# YARC_ID_Timer.net
KiCad netlist of a schematic drawn in EAGLE
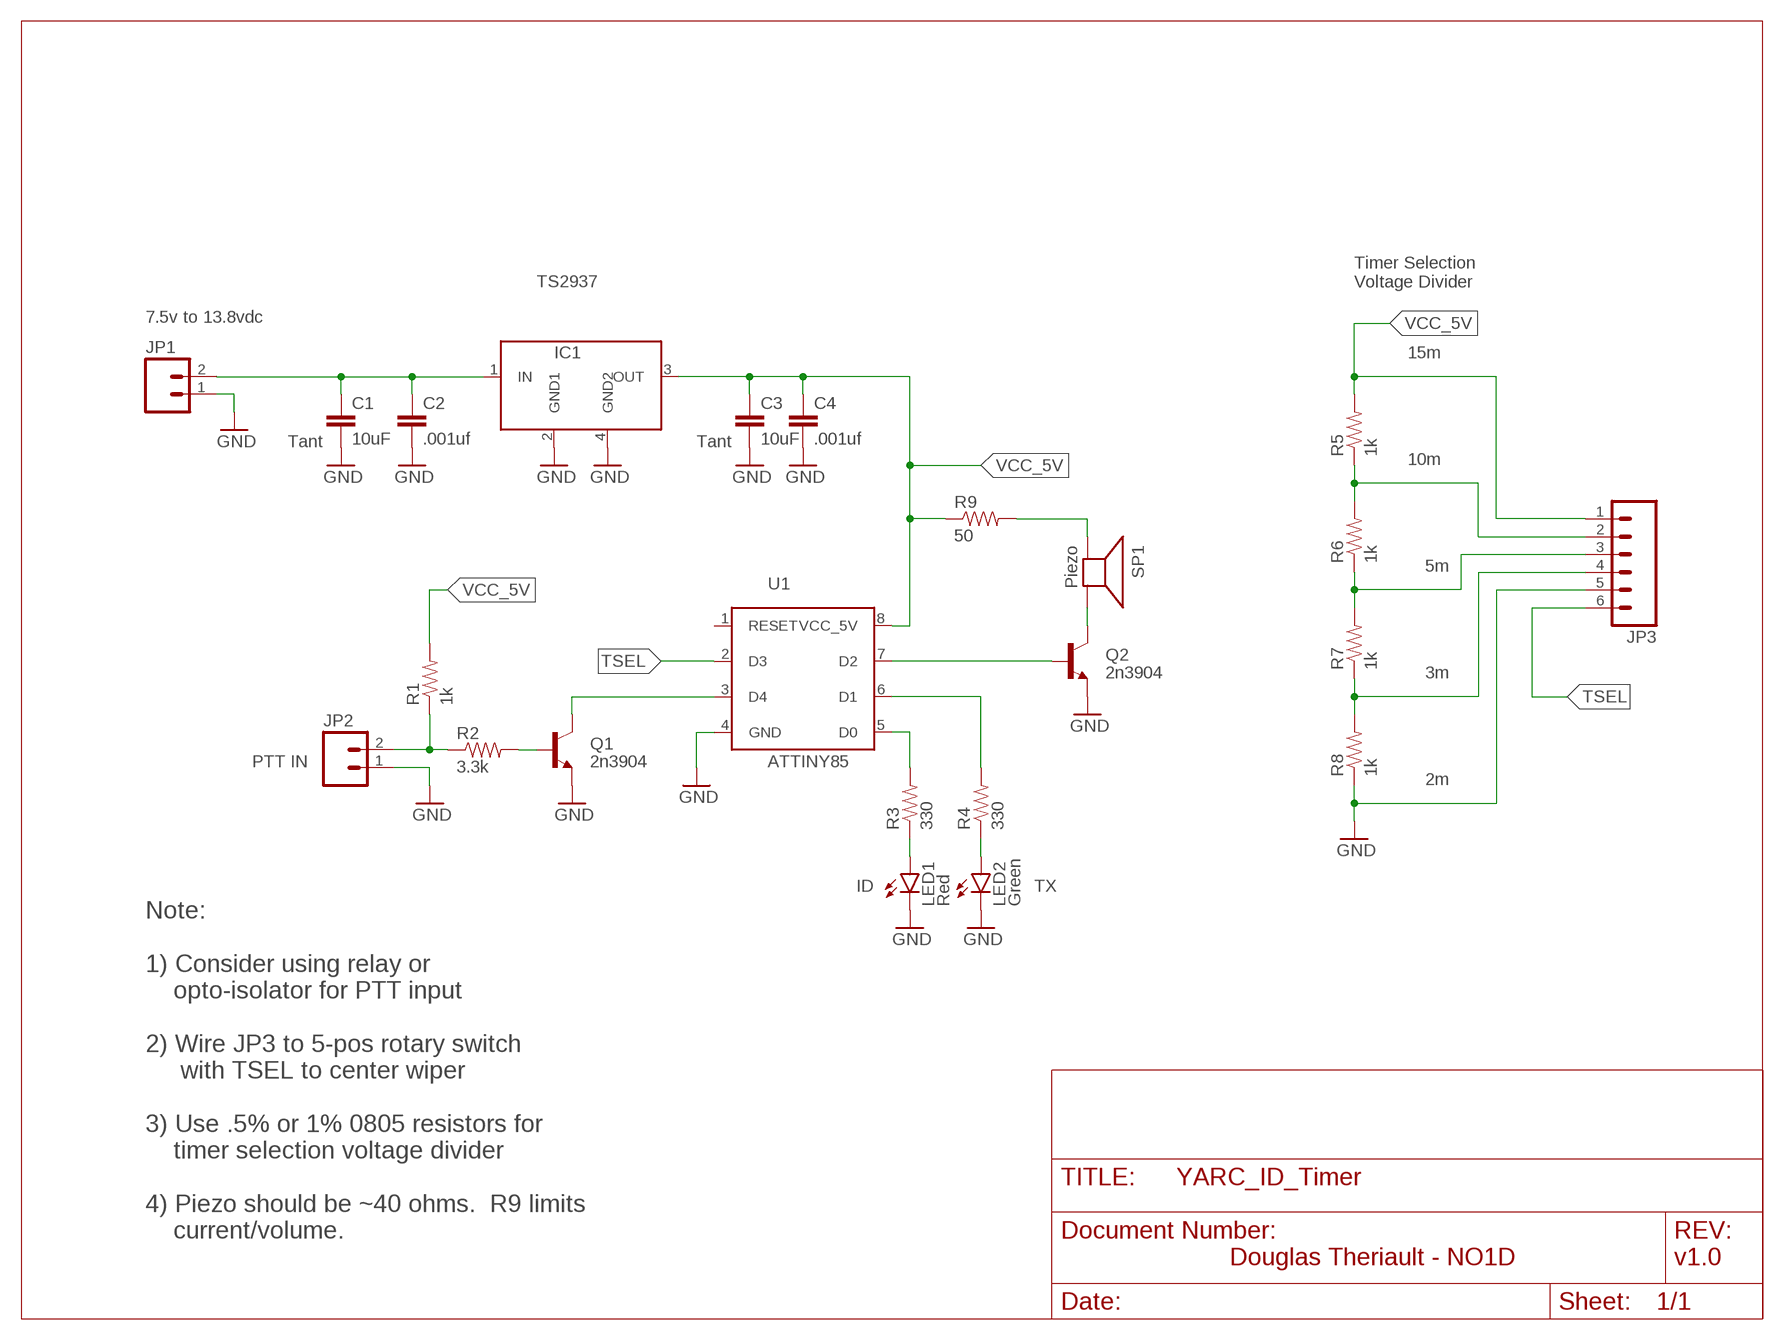
[diagram p0: schematic, sheet 1]

(export (version "E")
  (design (tool "Eeschema 10.0.6"))
  (components
    (comp (ref "C1")
      (value "10uF")
      (footprint "eagle-import:1210")
      (libsource (lib "eagle-import") (part "CAP1210"))
    )
    (comp (ref "C2")
      (value ".001uf")
      (footprint "eagle-import:0805")
      (libsource (lib "eagle-import") (part "CAP0805"))
    )
    (comp (ref "C3")
      (value "10uF")
      (footprint "eagle-import:0805")
      (libsource (lib "eagle-import") (part "CAP0805"))
    )
    (comp (ref "C4")
      (value ".001uf")
      (footprint "eagle-import:0805")
      (libsource (lib "eagle-import") (part "CAP0805"))
    )
    (comp (ref "IC1")
      (value "TS2937")
      (footprint "eagle-import:SOT223")
      (libsource (lib "eagle-import") (part "TS2937"))
    )
    (comp (ref "JP1")
      (value "M02LOCK_LONGPADS")
      (footprint "eagle-import:1X02_LOCK_LONGPADS")
      (libsource (lib "eagle-import") (part "M02LOCK_LONGPADS"))
    )
    (comp (ref "JP2")
      (value "M02LOCK_LONGPADS")
      (footprint "eagle-import:1X02_LOCK_LONGPADS")
      (libsource (lib "eagle-import") (part "M02LOCK_LONGPADS"))
    )
    (comp (ref "JP3")
      (value "M06LONGPADS")
      (footprint "eagle-import:1X06_LONGPADS")
      (libsource (lib "eagle-import") (part "M06LONGPADS"))
    )
    (comp (ref "LED1")
      (value "Red")
      (footprint "eagle-import:LED5MM")
      (libsource (lib "eagle-import") (part "LED5MM"))
    )
    (comp (ref "LED2")
      (value "Green")
      (footprint "eagle-import:LED5MM")
      (libsource (lib "eagle-import") (part "LED5MM"))
    )
    (comp (ref "Q1")
      (value "2n3904")
      (footprint "eagle-import:TO-92")
      (libsource (lib "eagle-import") (part "TRANSISTOR_NPN2N3904"))
    )
    (comp (ref "Q2")
      (value "2n3904")
      (footprint "eagle-import:TO-92")
      (libsource (lib "eagle-import") (part "TRANSISTOR_NPN2N3904"))
    )
    (comp (ref "R1")
      (value "1k")
      (footprint "eagle-import:0805")
      (libsource (lib "eagle-import") (part "RESISTOR0805-RES"))
    )
    (comp (ref "R2")
      (value "3.3k")
      (footprint "eagle-import:0805")
      (libsource (lib "eagle-import") (part "RESISTOR0805-RES"))
    )
    (comp (ref "R3")
      (value "330")
      (footprint "eagle-import:0805")
      (libsource (lib "eagle-import") (part "RESISTOR0805-RES"))
    )
    (comp (ref "R4")
      (value "330")
      (footprint "eagle-import:0805")
      (libsource (lib "eagle-import") (part "RESISTOR0805-RES"))
    )
    (comp (ref "R5")
      (value "1k")
      (footprint "eagle-import:0805")
      (libsource (lib "eagle-import") (part "RESISTOR0805-RES"))
    )
    (comp (ref "R6")
      (value "1k")
      (footprint "eagle-import:0805")
      (libsource (lib "eagle-import") (part "RESISTOR0805-RES"))
    )
    (comp (ref "R7")
      (value "1k")
      (footprint "eagle-import:0805")
      (libsource (lib "eagle-import") (part "RESISTOR0805-RES"))
    )
    (comp (ref "R8")
      (value "1k")
      (footprint "eagle-import:0805")
      (libsource (lib "eagle-import") (part "RESISTOR0805-RES"))
    )
    (comp (ref "R9")
      (value "50")
      (footprint "eagle-import:0805")
      (libsource (lib "eagle-import") (part "RESISTOR0805-RES"))
    )
    (comp (ref "SP1")
      (value "Piezo")
      (footprint "eagle-import:AL60P")
      (libsource (lib "eagle-import") (part "SPEAKER/AL60P"))
    )
    (comp (ref "U1")
      (value "ATTINY85")
      (footprint "eagle-import:DIP08")
      (libsource (lib "eagle-import") (part "ATTINY85"))
    )
  )
  (nets
    (net (code "1") (name "GND") (class "Default")
      (node (ref "C1") (pin "2") (pinfunction "2_2") (pintype "passive"))
      (node (ref "C2") (pin "2") (pinfunction "2_2") (pintype "passive"))
      (node (ref "C3") (pin "2") (pinfunction "2_2") (pintype "passive"))
      (node (ref "C4") (pin "2") (pinfunction "2_2") (pintype "passive"))
      (node (ref "IC1") (pin "2") (pinfunction "GND1_2") (pintype "bidirectional"))
      (node (ref "IC1") (pin "4") (pinfunction "GND2_4") (pintype "bidirectional"))
      (node (ref "JP1") (pin "1") (pinfunction "1_1") (pintype "passive"))
      (node (ref "JP2") (pin "1") (pinfunction "1_1") (pintype "passive"))
      (node (ref "JP3") (pin "5") (pinfunction "5_5") (pintype "passive"))
      (node (ref "LED1") (pin "K") (pinfunction "C_K") (pintype "passive"))
      (node (ref "LED2") (pin "K") (pinfunction "C_K") (pintype "passive"))
      (node (ref "Q1") (pin "1") (pinfunction "E_1") (pintype "passive"))
      (node (ref "Q2") (pin "1") (pinfunction "E_1") (pintype "passive"))
      (node (ref "R8") (pin "1") (pinfunction "1_1") (pintype "passive"))
      (node (ref "U1") (pin "4") (pinfunction "GND_4") (pintype "bidirectional"))
    )
    (net (code "2") (name "Net-(IC1-IN)") (class "Default")
      (node (ref "C1") (pin "1") (pinfunction "1_1") (pintype "passive"))
      (node (ref "C2") (pin "1") (pinfunction "1_1") (pintype "passive"))
      (node (ref "IC1") (pin "1") (pinfunction "IN_1") (pintype "bidirectional"))
      (node (ref "JP1") (pin "2") (pinfunction "2_2") (pintype "passive"))
    )
    (net (code "3") (name "Net-(JP2-Pad2)") (class "Default")
      (node (ref "JP2") (pin "2") (pinfunction "2_2") (pintype "passive"))
      (node (ref "R1") (pin "1") (pinfunction "1_1") (pintype "passive"))
      (node (ref "R2") (pin "1") (pinfunction "1_1") (pintype "passive"))
    )
    (net (code "4") (name "Net-(JP3-Pad2)") (class "Default")
      (node (ref "JP3") (pin "2") (pinfunction "2_2") (pintype "passive"))
      (node (ref "R5") (pin "1") (pinfunction "1_1") (pintype "passive"))
      (node (ref "R6") (pin "2") (pinfunction "2_2") (pintype "passive"))
    )
    (net (code "5") (name "Net-(JP3-Pad3)") (class "Default")
      (node (ref "JP3") (pin "3") (pinfunction "3_3") (pintype "passive"))
      (node (ref "R6") (pin "1") (pinfunction "1_1") (pintype "passive"))
      (node (ref "R7") (pin "2") (pinfunction "2_2") (pintype "passive"))
    )
    (net (code "6") (name "Net-(JP3-Pad4)") (class "Default")
      (node (ref "JP3") (pin "4") (pinfunction "4_4") (pintype "passive"))
      (node (ref "R7") (pin "1") (pinfunction "1_1") (pintype "passive"))
      (node (ref "R8") (pin "2") (pinfunction "2_2") (pintype "passive"))
    )
    (net (code "7") (name "Net-(LED1-PadA)") (class "Default")
      (node (ref "LED1") (pin "A") (pinfunction "A_A") (pintype "passive"))
      (node (ref "R3") (pin "1") (pinfunction "1_1") (pintype "passive"))
    )
    (net (code "8") (name "Net-(LED2-PadA)") (class "Default")
      (node (ref "LED2") (pin "A") (pinfunction "A_A") (pintype "passive"))
      (node (ref "R4") (pin "1") (pinfunction "1_1") (pintype "passive"))
    )
    (net (code "9") (name "Net-(Q1-B)") (class "Default")
      (node (ref "Q1") (pin "2") (pinfunction "B_2") (pintype "passive"))
      (node (ref "R2") (pin "2") (pinfunction "2_2") (pintype "passive"))
    )
    (net (code "10") (name "Net-(Q1-C)") (class "Default")
      (node (ref "Q1") (pin "3") (pinfunction "C_3") (pintype "passive"))
      (node (ref "U1") (pin "3") (pinfunction "D4_3") (pintype "bidirectional"))
    )
    (net (code "11") (name "Net-(Q2-B)") (class "Default")
      (node (ref "Q2") (pin "2") (pinfunction "B_2") (pintype "passive"))
      (node (ref "U1") (pin "7") (pinfunction "D2_7") (pintype "bidirectional"))
    )
    (net (code "12") (name "Net-(Q2-C)") (class "Default")
      (node (ref "Q2") (pin "3") (pinfunction "C_3") (pintype "passive"))
      (node (ref "SP1") (pin "2") (pinfunction "-_2") (pintype "passive"))
    )
    (net (code "13") (name "Net-(SP1-+)") (class "Default")
      (node (ref "R9") (pin "2") (pinfunction "2_2") (pintype "passive"))
      (node (ref "SP1") (pin "1") (pinfunction "+_1") (pintype "passive"))
    )
    (net (code "14") (name "Net-(U1-D0)") (class "Default")
      (node (ref "R3") (pin "2") (pinfunction "2_2") (pintype "passive"))
      (node (ref "U1") (pin "5") (pinfunction "D0_5") (pintype "bidirectional"))
    )
    (net (code "15") (name "Net-(U1-D1)") (class "Default")
      (node (ref "R4") (pin "2") (pinfunction "2_2") (pintype "passive"))
      (node (ref "U1") (pin "6") (pinfunction "D1_6") (pintype "bidirectional"))
    )
    (net (code "16") (name "TSEL") (class "Default")
      (node (ref "JP3") (pin "6") (pinfunction "6_6") (pintype "passive"))
      (node (ref "U1") (pin "2") (pinfunction "D3_2") (pintype "bidirectional"))
    )
    (net (code "17") (name "VCC_5V") (class "Default")
      (node (ref "C3") (pin "1") (pinfunction "1_1") (pintype "passive"))
      (node (ref "C4") (pin "1") (pinfunction "1_1") (pintype "passive"))
      (node (ref "IC1") (pin "3") (pinfunction "OUT_3") (pintype "bidirectional"))
      (node (ref "JP3") (pin "1") (pinfunction "1_1") (pintype "passive"))
      (node (ref "R1") (pin "2") (pinfunction "2_2") (pintype "passive"))
      (node (ref "R5") (pin "2") (pinfunction "2_2") (pintype "passive"))
      (node (ref "R9") (pin "1") (pinfunction "1_1") (pintype "passive"))
      (node (ref "U1") (pin "8") (pinfunction "VCC_5V_8") (pintype "bidirectional"))
    )
    (net (code "18") (name "unconnected-(U1-RESET-Pad1)") (class "Default")
      (node (ref "U1") (pin "1") (pinfunction "RESET_1") (pintype "bidirectional"))
    )
  )
)
